# rascsi-right.net
KiCad netlist of a schematic drawn in EAGLE
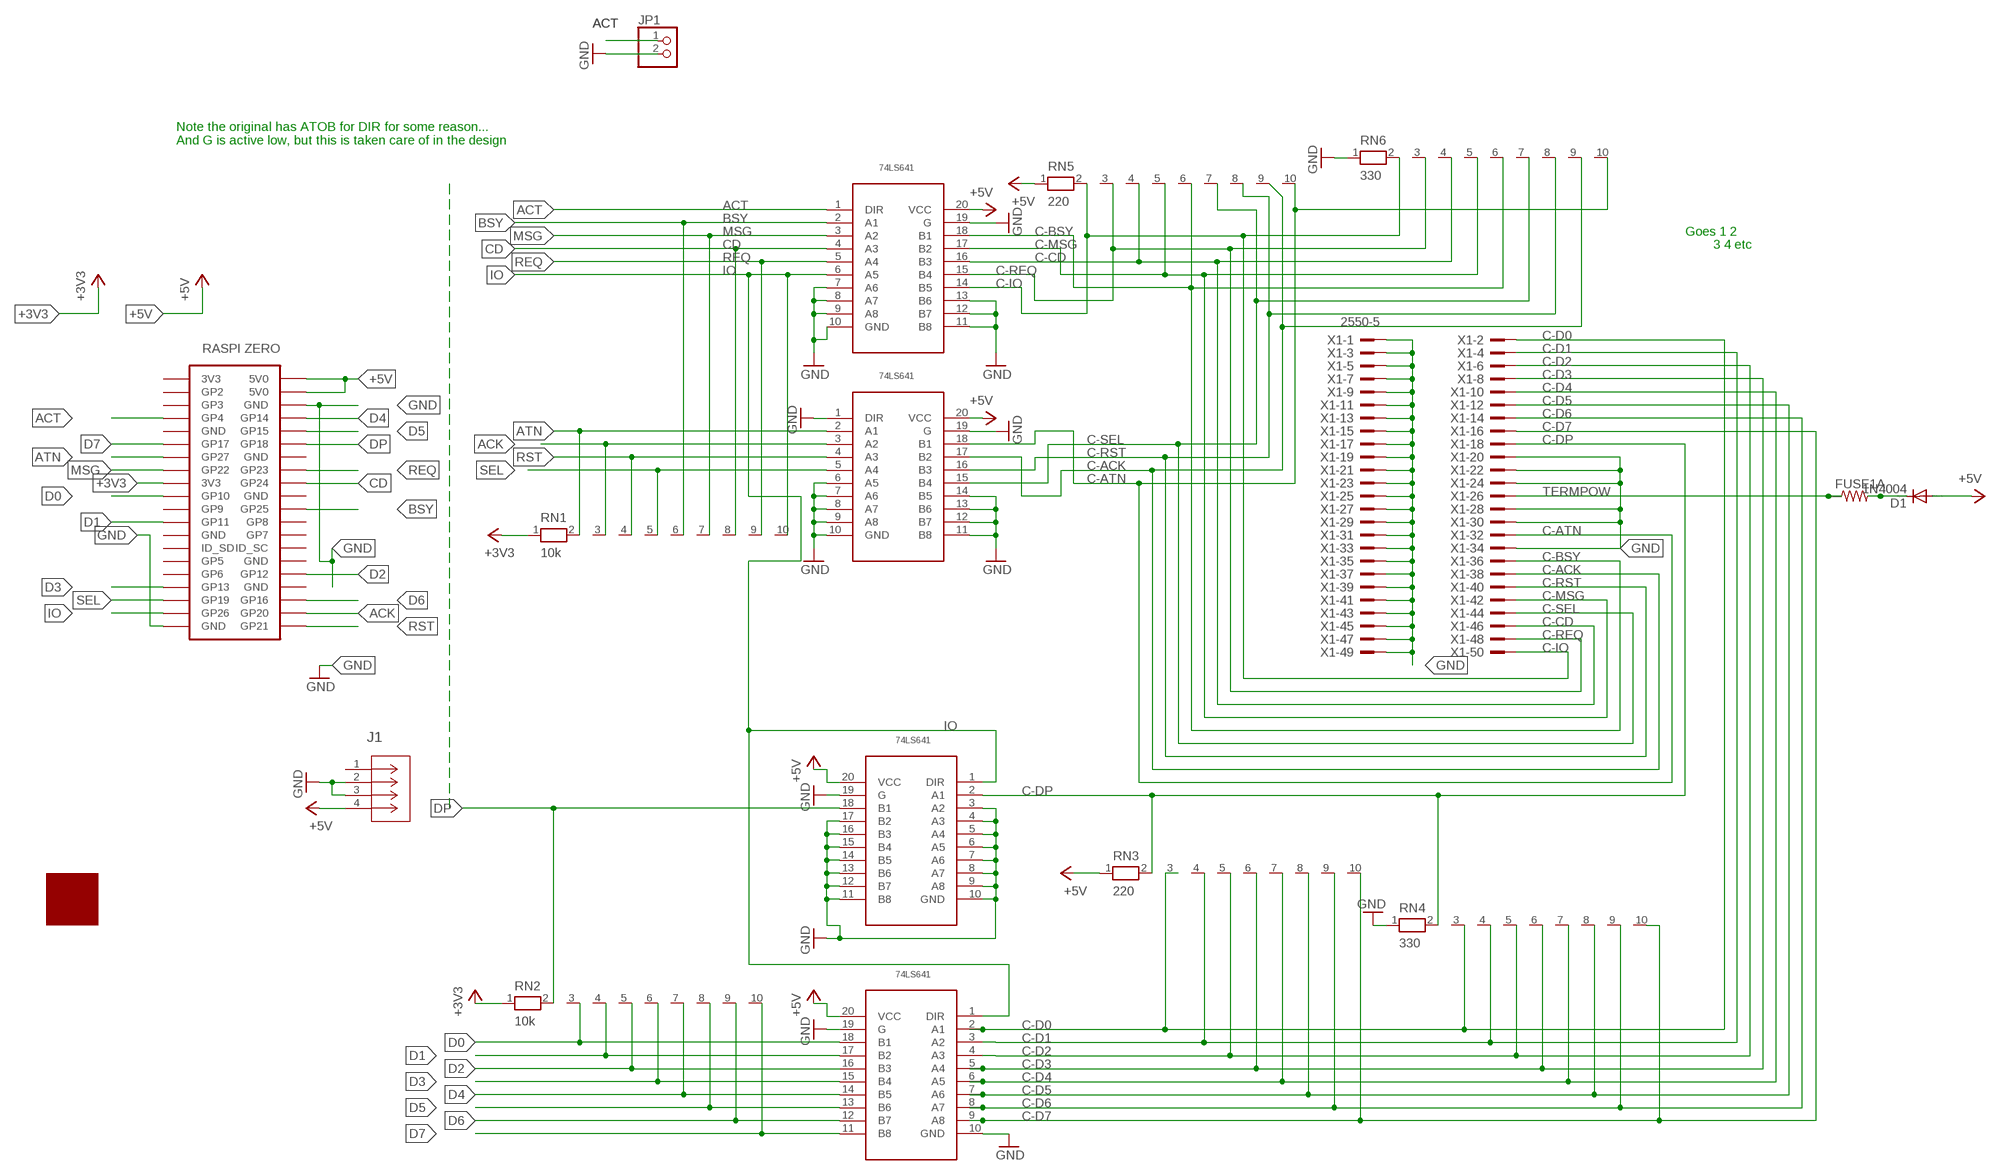
[diagram p0: schematic, sheet 1]

(export (version "E")
  (design (tool "Eeschema 10.0.6"))
  (components
    (comp (ref "D1")
      (value "1N4004")
      (footprint "eagle-import:DO41-10")
      (libsource (lib "eagle-import") (part "1N4004"))
    )
    (comp (ref "FUSE1A")
      (value "R-US_0204/7")
      (footprint "eagle-import:0204_7")
      (libsource (lib "eagle-import") (part "R-US_0204/7"))
    )
    (comp (ref "J1")
      (value "171826-4")
      (footprint "eagle-import:CONN_171826-4_TYCO")
      (fields (field (name "MANUFACTURER_PART_NUMBER") "1718264"))
      (libsource (lib "eagle-import") (part "171826-4"))
    )
    (comp (ref "JP1")
      (value "PINHD-1X2")
      (footprint "eagle-import:1X02")
      (libsource (lib "eagle-import") (part "PINHD-1X2"))
    )
    (comp (ref "RN1")
      (value "10k")
      (footprint "eagle-import:RN-10")
      (libsource (lib "eagle-import") (part "RN09"))
    )
    (comp (ref "RN2")
      (value "10k")
      (footprint "eagle-import:RN-10")
      (libsource (lib "eagle-import") (part "RN09"))
    )
    (comp (ref "RN3")
      (value "220")
      (footprint "eagle-import:RN-10")
      (libsource (lib "eagle-import") (part "RN09"))
    )
    (comp (ref "RN4")
      (value "330")
      (footprint "eagle-import:RN-10")
      (libsource (lib "eagle-import") (part "RN09"))
    )
    (comp (ref "RN5")
      (value "220")
      (footprint "eagle-import:RN-10")
      (libsource (lib "eagle-import") (part "RN09"))
    )
    (comp (ref "RN6")
      (value "330")
      (footprint "eagle-import:RN-10")
      (libsource (lib "eagle-import") (part "RN09"))
    )
    (comp (ref "U$1")
      (value "ZERO")
      (footprint "eagle-import:ZERO")
      (libsource (lib "eagle-import") (part "ZERO"))
    )
    (comp (ref "U$2")
      (value "LOGO")
      (footprint "eagle-import:LOGO")
      (libsource (lib "eagle-import") (part "LOGO"))
    )
    (comp (ref "U11")
      (value "SN74LS641-1SC")
      (footprint "eagle-import:SOIC20S")
      (libsource (lib "eagle-import") (part "SN74LS641-1CS"))
    )
    (comp (ref "U22")
      (value "SN74LS641-1SC")
      (footprint "eagle-import:SOIC20S")
      (libsource (lib "eagle-import") (part "SN74LS641-1CS"))
    )
    (comp (ref "U33")
      (value "SN74LS641-1SC")
      (footprint "eagle-import:SOIC20S")
      (libsource (lib "eagle-import") (part "SN74LS641-1CS"))
    )
    (comp (ref "U44")
      (value "SN74LS641-1SC")
      (footprint "eagle-import:SOIC20S")
      (libsource (lib "eagle-import") (part "SN74LS641-1CS"))
    )
    (comp (ref "X1")
      (value "2550-5")
      (footprint "eagle-import:PAK100_2500-5-50")
      (libsource (lib "eagle-import") (part "2550-5"))
    )
  )
  (nets
    (net (code "1") (name "+3V3") (class "Default")
      (node (ref "RN1") (pin "1") (pinfunction "1_1") (pintype "passive"))
      (node (ref "RN2") (pin "1") (pinfunction "1_1") (pintype "passive"))
      (node (ref "U$1") (pin "17") (pinfunction "3V3_17") (pintype "bidirectional"))
    )
    (net (code "2") (name "+5V") (class "Default")
      (node (ref "D1") (pin "A") (pinfunction "A_A") (pintype "passive"))
      (node (ref "J1") (pin "4") (pinfunction "4_4") (pintype "passive"))
      (node (ref "RN3") (pin "1") (pinfunction "1_1") (pintype "passive"))
      (node (ref "RN5") (pin "1") (pinfunction "1_1") (pintype "passive"))
      (node (ref "U$1") (pin "2") (pinfunction "5V0_2") (pintype "bidirectional"))
      (node (ref "U$1") (pin "4") (pinfunction "5V0_4") (pintype "bidirectional"))
      (node (ref "U11") (pin "20") (pinfunction "VCC_20") (pintype "power_in"))
      (node (ref "U22") (pin "20") (pinfunction "VCC_20") (pintype "power_in"))
      (node (ref "U33") (pin "20") (pinfunction "VCC_20") (pintype "power_in"))
      (node (ref "U44") (pin "20") (pinfunction "VCC_20") (pintype "power_in"))
    )
    (net (code "3") (name "/C-ACK") (class "Default")
      (node (ref "RN5") (pin "9") (pinfunction "9_9") (pintype "passive"))
      (node (ref "RN6") (pin "9") (pinfunction "9_9") (pintype "passive"))
      (node (ref "U22") (pin "17") (pinfunction "B2_17") (pintype "bidirectional"))
      (node (ref "X1") (pin "38") (pinfunction "KL_38") (pintype "passive"))
    )
    (net (code "4") (name "/C-ATN") (class "Default")
      (node (ref "RN5") (pin "10") (pinfunction "10_10") (pintype "passive"))
      (node (ref "RN6") (pin "10") (pinfunction "10_10") (pintype "passive"))
      (node (ref "U22") (pin "18") (pinfunction "B1_18") (pintype "bidirectional"))
      (node (ref "X1") (pin "32") (pinfunction "KL_32") (pintype "passive"))
    )
    (net (code "5") (name "/C-BSY") (class "Default")
      (node (ref "RN5") (pin "6") (pinfunction "6_6") (pintype "passive"))
      (node (ref "RN6") (pin "6") (pinfunction "6_6") (pintype "passive"))
      (node (ref "U11") (pin "18") (pinfunction "B1_18") (pintype "bidirectional"))
      (node (ref "X1") (pin "36") (pinfunction "KL_36") (pintype "passive"))
    )
    (net (code "6") (name "/C-CD") (class "Default")
      (node (ref "RN5") (pin "4") (pinfunction "4_4") (pintype "passive"))
      (node (ref "RN6") (pin "4") (pinfunction "4_4") (pintype "passive"))
      (node (ref "U11") (pin "16") (pinfunction "B3_16") (pintype "bidirectional"))
      (node (ref "X1") (pin "46") (pinfunction "KL_46") (pintype "passive"))
    )
    (net (code "7") (name "/C-D0") (class "Default")
      (node (ref "RN3") (pin "3") (pinfunction "3_3") (pintype "passive"))
      (node (ref "RN4") (pin "3") (pinfunction "3_3") (pintype "passive"))
      (node (ref "U44") (pin "2") (pinfunction "A1_2") (pintype "bidirectional"))
      (node (ref "X1") (pin "2") (pinfunction "KL_2") (pintype "passive"))
    )
    (net (code "8") (name "/C-D1") (class "Default")
      (node (ref "RN3") (pin "4") (pinfunction "4_4") (pintype "passive"))
      (node (ref "RN4") (pin "4") (pinfunction "4_4") (pintype "passive"))
      (node (ref "U44") (pin "3") (pinfunction "A2_3") (pintype "bidirectional"))
      (node (ref "X1") (pin "4") (pinfunction "KL_4") (pintype "passive"))
    )
    (net (code "9") (name "/C-D2") (class "Default")
      (node (ref "RN3") (pin "5") (pinfunction "5_5") (pintype "passive"))
      (node (ref "RN4") (pin "5") (pinfunction "5_5") (pintype "passive"))
      (node (ref "U44") (pin "4") (pinfunction "A3_4") (pintype "bidirectional"))
      (node (ref "X1") (pin "6") (pinfunction "KL_6") (pintype "passive"))
    )
    (net (code "10") (name "/C-D3") (class "Default")
      (node (ref "RN3") (pin "6") (pinfunction "6_6") (pintype "passive"))
      (node (ref "RN4") (pin "6") (pinfunction "6_6") (pintype "passive"))
      (node (ref "U44") (pin "5") (pinfunction "A4_5") (pintype "bidirectional"))
      (node (ref "X1") (pin "8") (pinfunction "KL_8") (pintype "passive"))
    )
    (net (code "11") (name "/C-D4") (class "Default")
      (node (ref "RN3") (pin "7") (pinfunction "7_7") (pintype "passive"))
      (node (ref "RN4") (pin "7") (pinfunction "7_7") (pintype "passive"))
      (node (ref "U44") (pin "6") (pinfunction "A5_6") (pintype "bidirectional"))
      (node (ref "X1") (pin "10") (pinfunction "KL_10") (pintype "passive"))
    )
    (net (code "12") (name "/C-D5") (class "Default")
      (node (ref "RN3") (pin "8") (pinfunction "8_8") (pintype "passive"))
      (node (ref "RN4") (pin "8") (pinfunction "8_8") (pintype "passive"))
      (node (ref "U44") (pin "7") (pinfunction "A6_7") (pintype "bidirectional"))
      (node (ref "X1") (pin "12") (pinfunction "KL_12") (pintype "passive"))
    )
    (net (code "13") (name "/C-D6") (class "Default")
      (node (ref "RN3") (pin "9") (pinfunction "9_9") (pintype "passive"))
      (node (ref "RN4") (pin "9") (pinfunction "9_9") (pintype "passive"))
      (node (ref "U44") (pin "8") (pinfunction "A7_8") (pintype "bidirectional"))
      (node (ref "X1") (pin "14") (pinfunction "KL_14") (pintype "passive"))
    )
    (net (code "14") (name "/C-D7") (class "Default")
      (node (ref "RN3") (pin "10") (pinfunction "10_10") (pintype "passive"))
      (node (ref "RN4") (pin "10") (pinfunction "10_10") (pintype "passive"))
      (node (ref "U44") (pin "9") (pinfunction "A8_9") (pintype "bidirectional"))
      (node (ref "X1") (pin "16") (pinfunction "KL_16") (pintype "passive"))
    )
    (net (code "15") (name "/C-DP") (class "Default")
      (node (ref "RN3") (pin "2") (pinfunction "2_2") (pintype "passive"))
      (node (ref "RN4") (pin "2") (pinfunction "2_2") (pintype "passive"))
      (node (ref "U33") (pin "2") (pinfunction "A1_2") (pintype "bidirectional"))
      (node (ref "X1") (pin "18") (pinfunction "KL_18") (pintype "passive"))
    )
    (net (code "16") (name "/C-IO") (class "Default")
      (node (ref "RN5") (pin "2") (pinfunction "2_2") (pintype "passive"))
      (node (ref "RN6") (pin "2") (pinfunction "2_2") (pintype "passive"))
      (node (ref "U11") (pin "14") (pinfunction "B5_14") (pintype "bidirectional"))
      (node (ref "X1") (pin "50") (pinfunction "KL_50") (pintype "passive"))
    )
    (net (code "17") (name "/C-MSG") (class "Default")
      (node (ref "RN5") (pin "5") (pinfunction "5_5") (pintype "passive"))
      (node (ref "RN6") (pin "5") (pinfunction "5_5") (pintype "passive"))
      (node (ref "U11") (pin "17") (pinfunction "B2_17") (pintype "bidirectional"))
      (node (ref "X1") (pin "42") (pinfunction "KL_42") (pintype "passive"))
    )
    (net (code "18") (name "/C-REQ") (class "Default")
      (node (ref "RN5") (pin "3") (pinfunction "3_3") (pintype "passive"))
      (node (ref "RN6") (pin "3") (pinfunction "3_3") (pintype "passive"))
      (node (ref "U11") (pin "15") (pinfunction "B4_15") (pintype "bidirectional"))
      (node (ref "X1") (pin "48") (pinfunction "KL_48") (pintype "passive"))
    )
    (net (code "19") (name "/C-RST") (class "Default")
      (node (ref "RN5") (pin "8") (pinfunction "8_8") (pintype "passive"))
      (node (ref "RN6") (pin "8") (pinfunction "8_8") (pintype "passive"))
      (node (ref "U22") (pin "16") (pinfunction "B3_16") (pintype "bidirectional"))
      (node (ref "X1") (pin "40") (pinfunction "KL_40") (pintype "passive"))
    )
    (net (code "20") (name "/C-SEL") (class "Default")
      (node (ref "RN5") (pin "7") (pinfunction "7_7") (pintype "passive"))
      (node (ref "RN6") (pin "7") (pinfunction "7_7") (pintype "passive"))
      (node (ref "U22") (pin "15") (pinfunction "B4_15") (pintype "bidirectional"))
      (node (ref "X1") (pin "44") (pinfunction "KL_44") (pintype "passive"))
    )
    (net (code "21") (name "/TERMPOW") (class "Default")
      (node (ref "FUSE1A") (pin "1") (pinfunction "1_1") (pintype "passive"))
      (node (ref "X1") (pin "26") (pinfunction "KL_26") (pintype "passive"))
    )
    (net (code "22") (name "ACK") (class "Default")
      (node (ref "RN1") (pin "3") (pinfunction "3_3") (pintype "passive"))
      (node (ref "U$1") (pin "38") (pinfunction "GP20_38") (pintype "bidirectional"))
      (node (ref "U22") (pin "3") (pinfunction "A2_3") (pintype "bidirectional"))
    )
    (net (code "23") (name "ACT") (class "Default")
      (node (ref "JP1") (pin "1") (pinfunction "1_1") (pintype "passive"))
      (node (ref "U$1") (pin "7") (pinfunction "GP4_7") (pintype "bidirectional"))
      (node (ref "U11") (pin "1") (pinfunction "DIR_1") (pintype "bidirectional"))
    )
    (net (code "24") (name "ATN") (class "Default")
      (node (ref "RN1") (pin "2") (pinfunction "2_2") (pintype "passive"))
      (node (ref "U$1") (pin "13") (pinfunction "GP27_13") (pintype "bidirectional"))
      (node (ref "U22") (pin "2") (pinfunction "A1_2") (pintype "bidirectional"))
    )
    (net (code "25") (name "BSY") (class "Default")
      (node (ref "RN1") (pin "6") (pinfunction "6_6") (pintype "passive"))
      (node (ref "U$1") (pin "22") (pinfunction "GP25_22") (pintype "bidirectional"))
      (node (ref "U11") (pin "2") (pinfunction "A1_2") (pintype "bidirectional"))
    )
    (net (code "26") (name "CD") (class "Default")
      (node (ref "RN1") (pin "8") (pinfunction "8_8") (pintype "passive"))
      (node (ref "U$1") (pin "18") (pinfunction "GP24_18") (pintype "bidirectional"))
      (node (ref "U11") (pin "4") (pinfunction "A3_4") (pintype "bidirectional"))
    )
    (net (code "27") (name "D0") (class "Default")
      (node (ref "RN2") (pin "3") (pinfunction "3_3") (pintype "passive"))
      (node (ref "U$1") (pin "19") (pinfunction "GP10_19") (pintype "bidirectional"))
      (node (ref "U44") (pin "18") (pinfunction "B1_18") (pintype "bidirectional"))
    )
    (net (code "28") (name "D1") (class "Default")
      (node (ref "RN2") (pin "4") (pinfunction "4_4") (pintype "passive"))
      (node (ref "U$1") (pin "23") (pinfunction "GP11_23") (pintype "bidirectional"))
      (node (ref "U44") (pin "17") (pinfunction "B2_17") (pintype "bidirectional"))
    )
    (net (code "29") (name "D2") (class "Default")
      (node (ref "RN2") (pin "5") (pinfunction "5_5") (pintype "passive"))
      (node (ref "U$1") (pin "32") (pinfunction "GP12_32") (pintype "bidirectional"))
      (node (ref "U44") (pin "16") (pinfunction "B3_16") (pintype "bidirectional"))
    )
    (net (code "30") (name "D3") (class "Default")
      (node (ref "RN2") (pin "6") (pinfunction "6_6") (pintype "passive"))
      (node (ref "U$1") (pin "33") (pinfunction "GP13_33") (pintype "bidirectional"))
      (node (ref "U44") (pin "15") (pinfunction "B4_15") (pintype "bidirectional"))
    )
    (net (code "31") (name "D4") (class "Default")
      (node (ref "RN2") (pin "7") (pinfunction "7_7") (pintype "passive"))
      (node (ref "U$1") (pin "8") (pinfunction "GP14_8") (pintype "bidirectional"))
      (node (ref "U44") (pin "14") (pinfunction "B5_14") (pintype "bidirectional"))
    )
    (net (code "32") (name "D5") (class "Default")
      (node (ref "RN2") (pin "8") (pinfunction "8_8") (pintype "passive"))
      (node (ref "U$1") (pin "10") (pinfunction "GP15_10") (pintype "bidirectional"))
      (node (ref "U44") (pin "13") (pinfunction "B6_13") (pintype "bidirectional"))
    )
    (net (code "33") (name "D6") (class "Default")
      (node (ref "RN2") (pin "9") (pinfunction "9_9") (pintype "passive"))
      (node (ref "U$1") (pin "36") (pinfunction "GP16_36") (pintype "bidirectional"))
      (node (ref "U44") (pin "12") (pinfunction "B7_12") (pintype "bidirectional"))
    )
    (net (code "34") (name "D7") (class "Default")
      (node (ref "RN2") (pin "10") (pinfunction "10_10") (pintype "passive"))
      (node (ref "U$1") (pin "11") (pinfunction "GP17_11") (pintype "bidirectional"))
      (node (ref "U44") (pin "11") (pinfunction "B8_11") (pintype "bidirectional"))
    )
    (net (code "35") (name "DP") (class "Default")
      (node (ref "RN2") (pin "2") (pinfunction "2_2") (pintype "passive"))
      (node (ref "U$1") (pin "12") (pinfunction "GP18_12") (pintype "bidirectional"))
      (node (ref "U33") (pin "18") (pinfunction "B1_18") (pintype "bidirectional"))
    )
    (net (code "36") (name "GND") (class "Default")
      (node (ref "J1") (pin "2") (pinfunction "2_2") (pintype "passive"))
      (node (ref "J1") (pin "3") (pinfunction "3_3") (pintype "passive"))
      (node (ref "JP1") (pin "2") (pinfunction "2_2") (pintype "passive"))
      (node (ref "RN4") (pin "1") (pinfunction "1_1") (pintype "passive"))
      (node (ref "RN6") (pin "1") (pinfunction "1_1") (pintype "passive"))
      (node (ref "U$1") (pin "39") (pinfunction "GND_39") (pintype "bidirectional"))
      (node (ref "U$1") (pin "6") (pinfunction "GND_6") (pintype "bidirectional"))
      (node (ref "U11") (pin "10") (pinfunction "GND_10") (pintype "power_in"))
      (node (ref "U11") (pin "11") (pinfunction "B8_11") (pintype "bidirectional"))
      (node (ref "U11") (pin "12") (pinfunction "B7_12") (pintype "bidirectional"))
      (node (ref "U11") (pin "13") (pinfunction "B6_13") (pintype "bidirectional"))
      (node (ref "U11") (pin "19") (pinfunction "G_19") (pintype "bidirectional"))
      (node (ref "U11") (pin "7") (pinfunction "A6_7") (pintype "bidirectional"))
      (node (ref "U11") (pin "8") (pinfunction "A7_8") (pintype "bidirectional"))
      (node (ref "U11") (pin "9") (pinfunction "A8_9") (pintype "bidirectional"))
      (node (ref "U22") (pin "1") (pinfunction "DIR_1") (pintype "bidirectional"))
      (node (ref "U22") (pin "10") (pinfunction "GND_10") (pintype "power_in"))
      (node (ref "U22") (pin "11") (pinfunction "B8_11") (pintype "bidirectional"))
      (node (ref "U22") (pin "12") (pinfunction "B7_12") (pintype "bidirectional"))
      (node (ref "U22") (pin "13") (pinfunction "B6_13") (pintype "bidirectional"))
      (node (ref "U22") (pin "14") (pinfunction "B5_14") (pintype "bidirectional"))
      (node (ref "U22") (pin "19") (pinfunction "G_19") (pintype "bidirectional"))
      (node (ref "U22") (pin "6") (pinfunction "A5_6") (pintype "bidirectional"))
      (node (ref "U22") (pin "7") (pinfunction "A6_7") (pintype "bidirectional"))
      (node (ref "U22") (pin "8") (pinfunction "A7_8") (pintype "bidirectional"))
      (node (ref "U22") (pin "9") (pinfunction "A8_9") (pintype "bidirectional"))
      (node (ref "U33") (pin "10") (pinfunction "GND_10") (pintype "power_in"))
      (node (ref "U33") (pin "11") (pinfunction "B8_11") (pintype "bidirectional"))
      (node (ref "U33") (pin "12") (pinfunction "B7_12") (pintype "bidirectional"))
      (node (ref "U33") (pin "13") (pinfunction "B6_13") (pintype "bidirectional"))
      (node (ref "U33") (pin "14") (pinfunction "B5_14") (pintype "bidirectional"))
      (node (ref "U33") (pin "15") (pinfunction "B4_15") (pintype "bidirectional"))
      (node (ref "U33") (pin "16") (pinfunction "B3_16") (pintype "bidirectional"))
      (node (ref "U33") (pin "17") (pinfunction "B2_17") (pintype "bidirectional"))
      (node (ref "U33") (pin "19") (pinfunction "G_19") (pintype "bidirectional"))
      (node (ref "U33") (pin "3") (pinfunction "A2_3") (pintype "bidirectional"))
      (node (ref "U33") (pin "4") (pinfunction "A3_4") (pintype "bidirectional"))
      (node (ref "U33") (pin "5") (pinfunction "A4_5") (pintype "bidirectional"))
      (node (ref "U33") (pin "6") (pinfunction "A5_6") (pintype "bidirectional"))
      (node (ref "U33") (pin "7") (pinfunction "A6_7") (pintype "bidirectional"))
      (node (ref "U33") (pin "8") (pinfunction "A7_8") (pintype "bidirectional"))
      (node (ref "U33") (pin "9") (pinfunction "A8_9") (pintype "bidirectional"))
      (node (ref "U44") (pin "10") (pinfunction "GND_10") (pintype "power_in"))
      (node (ref "U44") (pin "19") (pinfunction "G_19") (pintype "bidirectional"))
      (node (ref "X1") (pin "1") (pinfunction "KL_1") (pintype "passive"))
      (node (ref "X1") (pin "11") (pinfunction "KL_11") (pintype "passive"))
      (node (ref "X1") (pin "13") (pinfunction "KL_13") (pintype "passive"))
      (node (ref "X1") (pin "15") (pinfunction "KL_15") (pintype "passive"))
      (node (ref "X1") (pin "17") (pinfunction "KL_17") (pintype "passive"))
      (node (ref "X1") (pin "19") (pinfunction "KL_19") (pintype "passive"))
      (node (ref "X1") (pin "20") (pinfunction "KL_20") (pintype "passive"))
      (node (ref "X1") (pin "21") (pinfunction "KL_21") (pintype "passive"))
      (node (ref "X1") (pin "22") (pinfunction "KL_22") (pintype "passive"))
      (node (ref "X1") (pin "23") (pinfunction "KL_23") (pintype "passive"))
      (node (ref "X1") (pin "24") (pinfunction "KL_24") (pintype "passive"))
      (node (ref "X1") (pin "25") (pinfunction "KL_25") (pintype "passive"))
      (node (ref "X1") (pin "27") (pinfunction "KL_27") (pintype "passive"))
      (node (ref "X1") (pin "28") (pinfunction "KL_28") (pintype "passive"))
      (node (ref "X1") (pin "29") (pinfunction "KL_29") (pintype "passive"))
      (node (ref "X1") (pin "3") (pinfunction "KL_3") (pintype "passive"))
      (node (ref "X1") (pin "30") (pinfunction "KL_30") (pintype "passive"))
      (node (ref "X1") (pin "31") (pinfunction "KL_31") (pintype "passive"))
      (node (ref "X1") (pin "33") (pinfunction "KL_33") (pintype "passive"))
      (node (ref "X1") (pin "34") (pinfunction "KL_34") (pintype "passive"))
      (node (ref "X1") (pin "35") (pinfunction "KL_35") (pintype "passive"))
      (node (ref "X1") (pin "37") (pinfunction "KL_37") (pintype "passive"))
      (node (ref "X1") (pin "39") (pinfunction "KL_39") (pintype "passive"))
      (node (ref "X1") (pin "41") (pinfunction "KL_41") (pintype "passive"))
      (node (ref "X1") (pin "43") (pinfunction "KL_43") (pintype "passive"))
      (node (ref "X1") (pin "45") (pinfunction "KL_45") (pintype "passive"))
      (node (ref "X1") (pin "47") (pinfunction "KL_47") (pintype "passive"))
      (node (ref "X1") (pin "49") (pinfunction "KL_49") (pintype "passive"))
      (node (ref "X1") (pin "5") (pinfunction "KL_5") (pintype "passive"))
      (node (ref "X1") (pin "7") (pinfunction "KL_7") (pintype "passive"))
      (node (ref "X1") (pin "9") (pinfunction "KL_9") (pintype "passive"))
    )
    (net (code "37") (name "IO") (class "Default")
      (node (ref "RN1") (pin "10") (pinfunction "10_10") (pintype "passive"))
      (node (ref "U$1") (pin "37") (pinfunction "GP26_37") (pintype "bidirectional"))
      (node (ref "U11") (pin "6") (pinfunction "A5_6") (pintype "bidirectional"))
      (node (ref "U33") (pin "1") (pinfunction "DIR_1") (pintype "bidirectional"))
      (node (ref "U44") (pin "1") (pinfunction "DIR_1") (pintype "bidirectional"))
    )
    (net (code "38") (name "MSG") (class "Default")
      (node (ref "RN1") (pin "7") (pinfunction "7_7") (pintype "passive"))
      (node (ref "U$1") (pin "15") (pinfunction "GP22_15") (pintype "bidirectional"))
      (node (ref "U11") (pin "3") (pinfunction "A2_3") (pintype "bidirectional"))
    )
    (net (code "39") (name "Net-(D1-PadC)") (class "Default")
      (node (ref "D1") (pin "C") (pinfunction "C_C") (pintype "passive"))
      (node (ref "FUSE1A") (pin "2") (pinfunction "2_2") (pintype "passive"))
    )
    (net (code "40") (name "REQ") (class "Default")
      (node (ref "RN1") (pin "9") (pinfunction "9_9") (pintype "passive"))
      (node (ref "U$1") (pin "16") (pinfunction "GP23_16") (pintype "bidirectional"))
      (node (ref "U11") (pin "5") (pinfunction "A4_5") (pintype "bidirectional"))
    )
    (net (code "41") (name "RST") (class "Default")
      (node (ref "RN1") (pin "4") (pinfunction "4_4") (pintype "passive"))
      (node (ref "U$1") (pin "40") (pinfunction "GP21_40") (pintype "bidirectional"))
      (node (ref "U22") (pin "4") (pinfunction "A3_4") (pintype "bidirectional"))
    )
    (net (code "42") (name "SEL") (class "Default")
      (node (ref "RN1") (pin "5") (pinfunction "5_5") (pintype "passive"))
      (node (ref "U$1") (pin "35") (pinfunction "GP19_35") (pintype "bidirectional"))
      (node (ref "U22") (pin "5") (pinfunction "A4_5") (pintype "bidirectional"))
    )
    (net (code "43") (name "unconnected-(J1-Pad1)") (class "Default")
      (node (ref "J1") (pin "1") (pinfunction "1_1") (pintype "passive"))
    )
    (net (code "44") (name "unconnected-(U$1-3V3-Pad1)") (class "Default")
      (node (ref "U$1") (pin "1") (pinfunction "3V3_1") (pintype "bidirectional"))
    )
    (net (code "45") (name "unconnected-(U$1-GND-Pad9)") (class "Default")
      (node (ref "U$1") (pin "9") (pinfunction "GND_9") (pintype "bidirectional"))
    )
    (net (code "46") (name "unconnected-(U$1-GND-Pad14)") (class "Default")
      (node (ref "U$1") (pin "14") (pinfunction "GND_14") (pintype "bidirectional"))
    )
    (net (code "47") (name "unconnected-(U$1-GND-Pad20)") (class "Default")
      (node (ref "U$1") (pin "20") (pinfunction "GND_20") (pintype "bidirectional"))
    )
    (net (code "48") (name "unconnected-(U$1-GND-Pad25)") (class "Default")
      (node (ref "U$1") (pin "25") (pinfunction "GND_25") (pintype "bidirectional"))
    )
    (net (code "49") (name "unconnected-(U$1-GND-Pad30)") (class "Default")
      (node (ref "U$1") (pin "30") (pinfunction "GND_30") (pintype "bidirectional"))
    )
    (net (code "50") (name "unconnected-(U$1-GND-Pad34)") (class "Default")
      (node (ref "U$1") (pin "34") (pinfunction "GND_34") (pintype "bidirectional"))
    )
    (net (code "51") (name "unconnected-(U$1-GP2-Pad3)") (class "Default")
      (node (ref "U$1") (pin "3") (pinfunction "GP2_3") (pintype "bidirectional"))
    )
    (net (code "52") (name "unconnected-(U$1-GP3-Pad5)") (class "Default")
      (node (ref "U$1") (pin "5") (pinfunction "GP3_5") (pintype "bidirectional"))
    )
    (net (code "53") (name "unconnected-(U$1-GP5-Pad29)") (class "Default")
      (node (ref "U$1") (pin "29") (pinfunction "GP5_29") (pintype "bidirectional"))
    )
    (net (code "54") (name "unconnected-(U$1-GP6-Pad31)") (class "Default")
      (node (ref "U$1") (pin "31") (pinfunction "GP6_31") (pintype "bidirectional"))
    )
    (net (code "55") (name "unconnected-(U$1-GP7-Pad26)") (class "Default")
      (node (ref "U$1") (pin "26") (pinfunction "GP7_26") (pintype "bidirectional"))
    )
    (net (code "56") (name "unconnected-(U$1-GP8-Pad24)") (class "Default")
      (node (ref "U$1") (pin "24") (pinfunction "GP8_24") (pintype "bidirectional"))
    )
    (net (code "57") (name "unconnected-(U$1-GP9-Pad21)") (class "Default")
      (node (ref "U$1") (pin "21") (pinfunction "GP9_21") (pintype "bidirectional"))
    )
    (net (code "58") (name "unconnected-(U$1-ID_SC-Pad28)") (class "Default")
      (node (ref "U$1") (pin "28") (pinfunction "ID_SC_28") (pintype "bidirectional"))
    )
    (net (code "59") (name "unconnected-(U$1-ID_SD-Pad27)") (class "Default")
      (node (ref "U$1") (pin "27") (pinfunction "ID_SD_27") (pintype "bidirectional"))
    )
  )
)
